# Vapeix_eeprom_test.net
KiCad netlist of a schematic drawn in Altium Designer
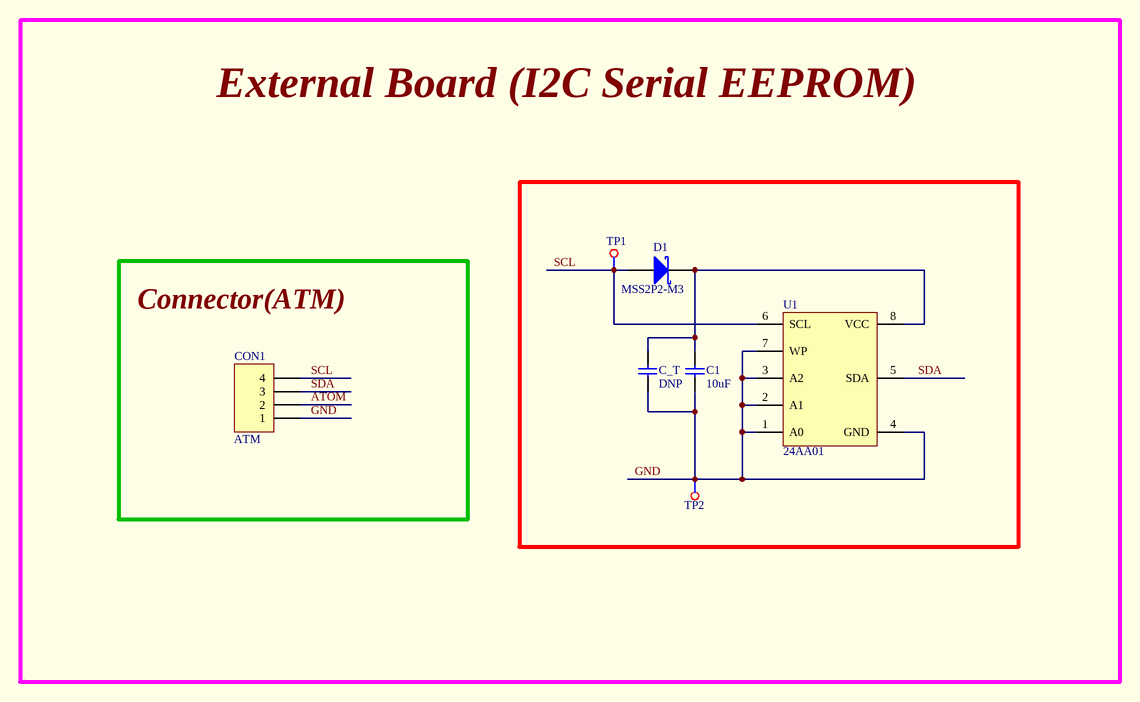
[diagram p0: Vapeix_eeprom_test.SchDoc]

(export (version "E")
  (design (tool "Eeschema 10.0.6"))
  (components
    (comp (ref "C1")
      (value "10uF")
      (footprint "C0402")
      (description "Capacitor, NP0, ±2%")
      (fields (field (name "PART NUMBER") "C0402-12p") (field (name "PUBLISHER") "Nordic Semiconductor"))
      (libsource (lib "Nordic Passive DB") (part "CAP"))
    )
    (comp (ref "CON1")
      (value "ATM")
      (footprint "S4B-PH-K-S")
      (description "CONN HEADER PH SIDE 4POS 2MM")
      (fields
        (field (name "MANUFACTURER") "JST Sales America Inc.")
        (field (name "MANUFACTURER PART NUMBER") "S4B-PH-K-S(LF)(SN)")
      )
      (libsource (lib "VapeixS_LIB") (part "S4B-PH-K-S(LF)(SN)"))
    )
    (comp (ref "C_T")
      (value "DNP")
      (footprint "C0201")
      (description "Capacitor, NP0, ±2%")
      (fields (field (name "PART NUMBER") "C0402-12p") (field (name "PUBLISHER") "Nordic Semiconductor"))
      (libsource (lib "Nordic Passive DB") (part "CAP"))
    )
    (comp (ref "D1")
      (value "MSS2P2-M3")
      (footprint "MSS2P2-M3")
      (description "DIODE SCHOTTKY 20V 2A MICROSMP")
      (fields
        (field (name "MANUFACTURER") "Vishay Semiconductor Diodes Division")
        (field (name "MANUFACTURER PART NUMBER") "MSS2P2-M3/89A")
      )
      (libsource (lib "VapeixS_LIB") (part "MSS2P2-M3/89A"))
    )
    (comp (ref "TP1")
      (value "TP")
      (footprint "TP")
      (description "TEST POINT")
      (libsource (lib "") (part "TP_1"))
    )
    (comp (ref "TP2")
      (value "TP")
      (footprint "TP")
      (description "TEST POINT")
      (libsource (lib "VapeixS_LIB") (part "TP"))
    )
    (comp (ref "U1")
      (value "24AA01")
      (footprint "24AA01")
      (description "IC EEPROM 1KBIT 400KHZ 8SOIC")
      (fields
        (field (name "MANUFACTURER") "Microchip Technology")
        (field (name "MANUFACTURER PART NUMBER") "24AA01-I/SN")
      )
      (libsource (lib "ExternalLib") (part "24AA01-I/SN"))
    )
  )
  (nets
    (net (code "1") (name "/ATOM") (class "Default")
      (node (ref "CON1") (pin "2") (pinfunction "2_2") (pintype "passive"))
    )
    (net (code "4") (name "/GND") (class "Default")
      (node (ref "C1") (pin "1") (pinfunction "1_1") (pintype "passive"))
      (node (ref "CON1") (pin "1") (pinfunction "1_1") (pintype "passive"))
      (node (ref "C_T") (pin "1") (pinfunction "1_1") (pintype "passive"))
      (node (ref "TP2") (pin "1") (pinfunction "TP_1") (pintype "passive"))
      (node (ref "U1") (pin "1") (pinfunction "A0_1") (pintype "passive"))
      (node (ref "U1") (pin "2") (pinfunction "A1_2") (pintype "passive"))
      (node (ref "U1") (pin "3") (pinfunction "A2_3") (pintype "passive"))
      (node (ref "U1") (pin "4") (pinfunction "GND_4") (pintype "passive"))
      (node (ref "U1") (pin "7") (pinfunction "WP_7") (pintype "passive"))
    )
    (net (code "5") (name "/SCL") (class "Default")
      (node (ref "CON1") (pin "4") (pinfunction "4_4") (pintype "passive"))
      (node (ref "D1") (pin "1") (pinfunction "A_1") (pintype "passive"))
      (node (ref "TP1") (pin "1") (pinfunction "TP_1") (pintype "passive"))
      (node (ref "U1") (pin "6") (pinfunction "SCL_6") (pintype "passive"))
    )
    (net (code "6") (name "/SDA") (class "Default")
      (node (ref "CON1") (pin "3") (pinfunction "3_3") (pintype "passive"))
      (node (ref "U1") (pin "5") (pinfunction "SDA_5") (pintype "passive"))
    )
    (net (code "7") (name "Net-(D1-K)") (class "Default")
      (node (ref "C1") (pin "2") (pinfunction "2_2") (pintype "passive"))
      (node (ref "C_T") (pin "2") (pinfunction "2_2") (pintype "passive"))
      (node (ref "D1") (pin "2") (pinfunction "K_2") (pintype "passive"))
      (node (ref "U1") (pin "8") (pinfunction "VCC_8") (pintype "passive"))
    )
  )
)
